# synchronizer_v1_1.net
KiCad netlist of a schematic drawn in EAGLE
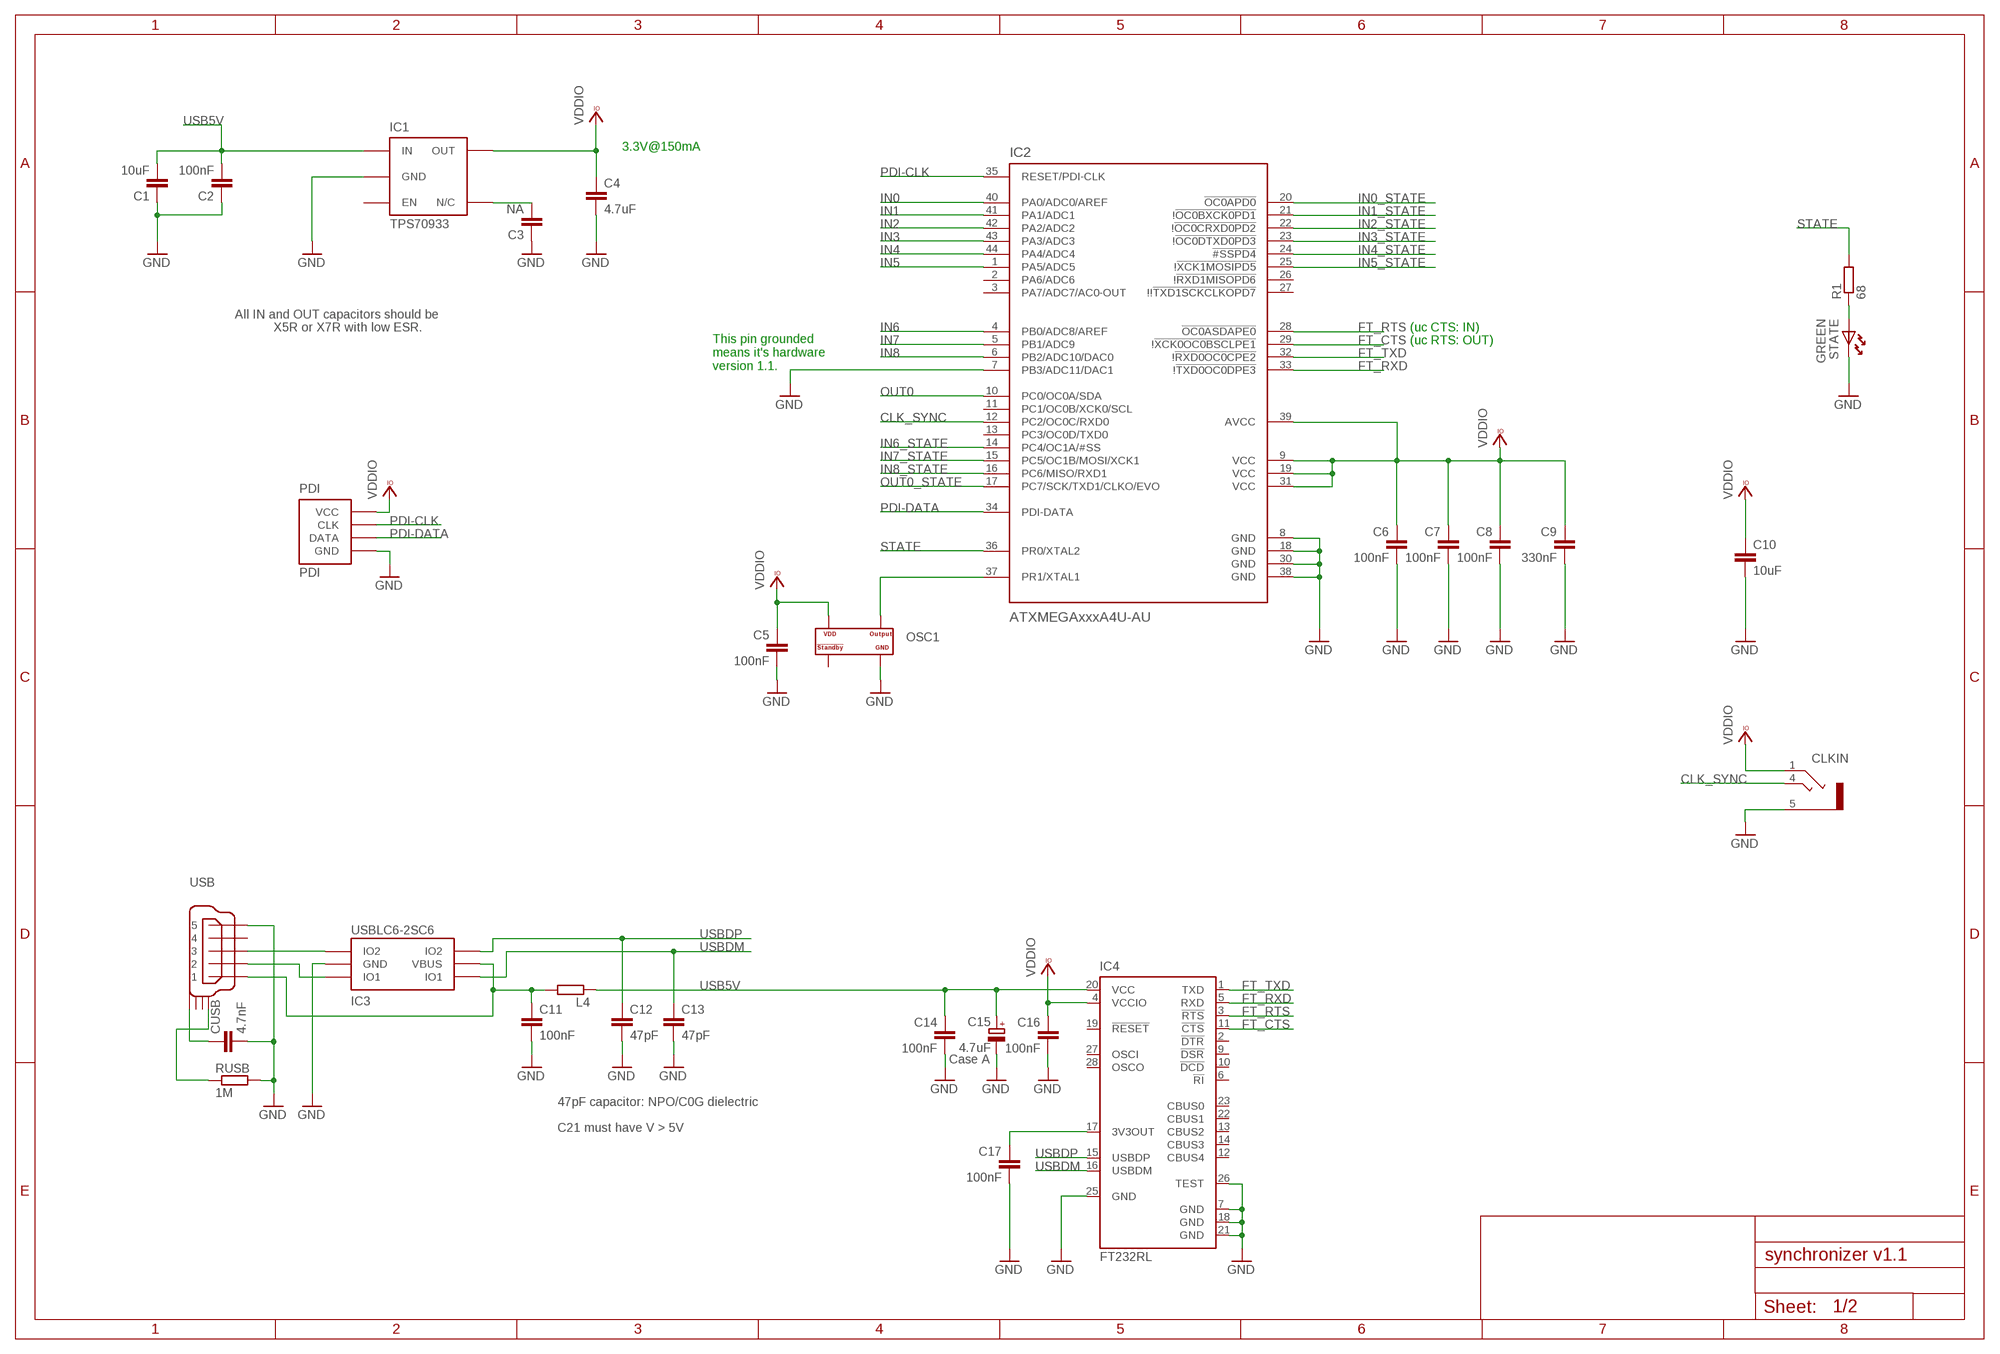
[diagram p0: schematic, sheet 1]
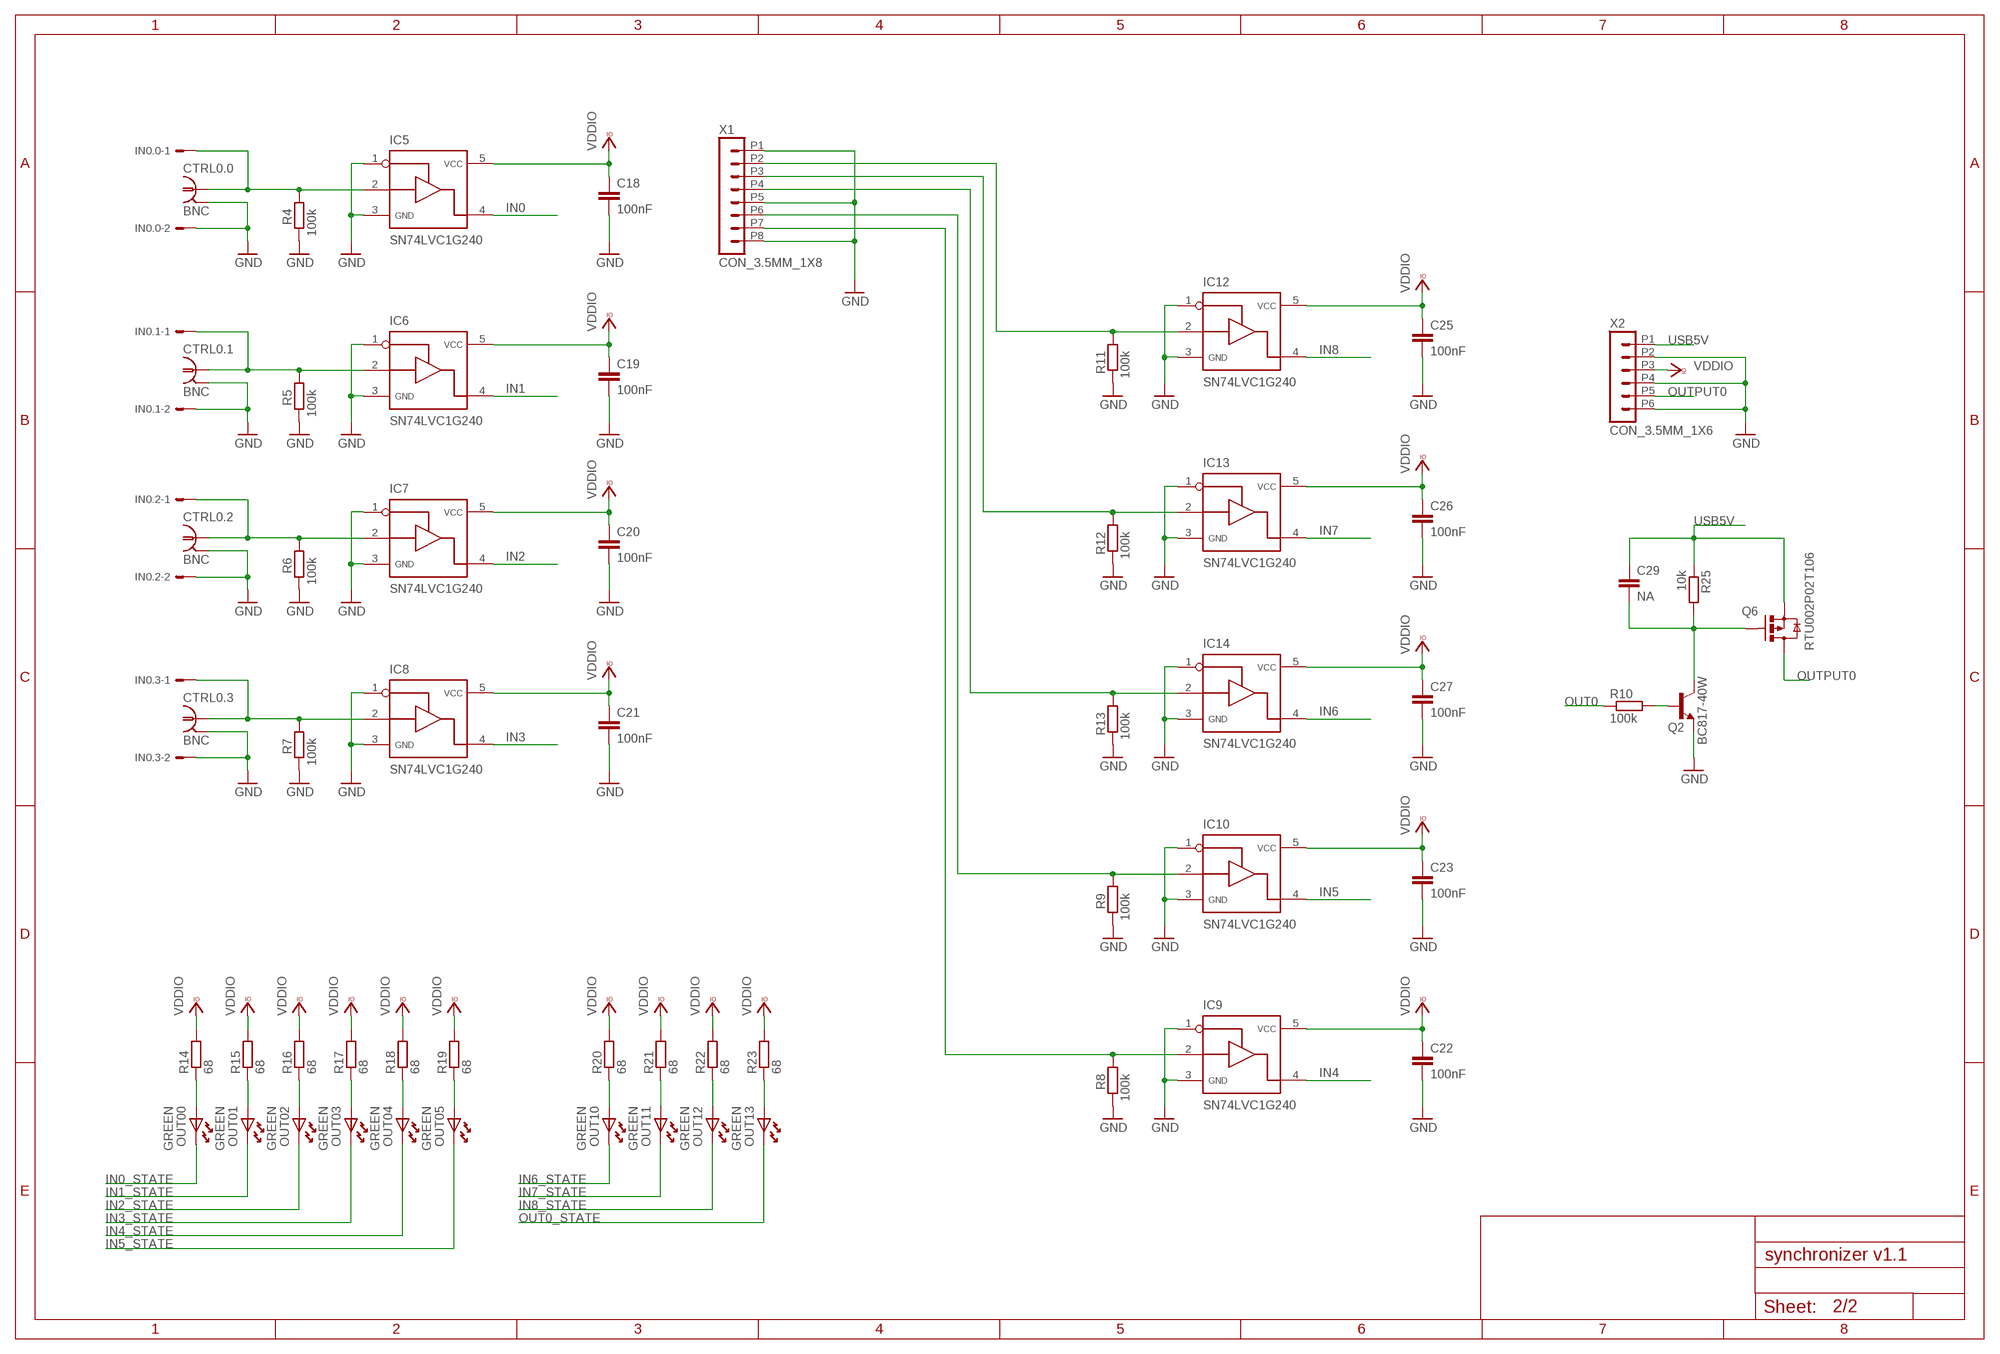
[diagram p1: schematic, sheet 2]

(export (version "E")
  (design (tool "Eeschema 10.0.6"))
  (components
    (comp (ref "C18")
      (value "100nF")
      (footprint "eagle-import:C0402")
      (libsource (lib "eagle-import") (part "C-EUC0402"))
    )
    (comp (ref "C19")
      (value "100nF")
      (footprint "eagle-import:C0402")
      (libsource (lib "eagle-import") (part "C-EUC0402"))
    )
    (comp (ref "C20")
      (value "100nF")
      (footprint "eagle-import:C0402")
      (libsource (lib "eagle-import") (part "C-EUC0402"))
    )
    (comp (ref "C21")
      (value "100nF")
      (footprint "eagle-import:C0402")
      (libsource (lib "eagle-import") (part "C-EUC0402"))
    )
    (comp (ref "C22")
      (value "100nF")
      (footprint "eagle-import:C0402")
      (libsource (lib "eagle-import") (part "C-EUC0402"))
    )
    (comp (ref "C23")
      (value "100nF")
      (footprint "eagle-import:C0402")
      (libsource (lib "eagle-import") (part "C-EUC0402"))
    )
    (comp (ref "C25")
      (value "100nF")
      (footprint "eagle-import:C0402")
      (libsource (lib "eagle-import") (part "C-EUC0402"))
    )
    (comp (ref "C26")
      (value "100nF")
      (footprint "eagle-import:C0402")
      (libsource (lib "eagle-import") (part "C-EUC0402"))
    )
    (comp (ref "C27")
      (value "100nF")
      (footprint "eagle-import:C0402")
      (libsource (lib "eagle-import") (part "C-EUC0402"))
    )
    (comp (ref "C29")
      (value "NA")
      (footprint "eagle-import:C0402")
      (libsource (lib "eagle-import") (part "C-EUC0402"))
    )
    (comp (ref "CTRL0.0")
      (value "BNC")
      (footprint "eagle-import:BNC_RA")
      (libsource (lib "eagle-import") (part "BNC"))
    )
    (comp (ref "CTRL0.1")
      (value "BNC")
      (footprint "eagle-import:BNC_RA")
      (libsource (lib "eagle-import") (part "BNC"))
    )
    (comp (ref "CTRL0.2")
      (value "BNC")
      (footprint "eagle-import:BNC_RA")
      (libsource (lib "eagle-import") (part "BNC"))
    )
    (comp (ref "CTRL0.3")
      (value "BNC")
      (footprint "eagle-import:BNC_RA")
      (libsource (lib "eagle-import") (part "BNC"))
    )
    (comp (ref "IC5")
      (value "SN74LVC1G240")
      (footprint "eagle-import:SOT23-5")
      (libsource (lib "eagle-import") (part "SN74LVC1G125"))
    )
    (comp (ref "IC6")
      (value "SN74LVC1G240")
      (footprint "eagle-import:SOT23-5")
      (libsource (lib "eagle-import") (part "SN74LVC1G125"))
    )
    (comp (ref "IC7")
      (value "SN74LVC1G240")
      (footprint "eagle-import:SOT23-5")
      (libsource (lib "eagle-import") (part "SN74LVC1G125"))
    )
    (comp (ref "IC8")
      (value "SN74LVC1G240")
      (footprint "eagle-import:SOT23-5")
      (libsource (lib "eagle-import") (part "SN74LVC1G125"))
    )
    (comp (ref "IC9")
      (value "SN74LVC1G240")
      (footprint "eagle-import:SOT23-5")
      (libsource (lib "eagle-import") (part "SN74LVC1G125"))
    )
    (comp (ref "IC10")
      (value "SN74LVC1G240")
      (footprint "eagle-import:SOT23-5")
      (libsource (lib "eagle-import") (part "SN74LVC1G125"))
    )
    (comp (ref "IC12")
      (value "SN74LVC1G240")
      (footprint "eagle-import:SOT23-5")
      (libsource (lib "eagle-import") (part "SN74LVC1G125"))
    )
    (comp (ref "IC13")
      (value "SN74LVC1G240")
      (footprint "eagle-import:SOT23-5")
      (libsource (lib "eagle-import") (part "SN74LVC1G125"))
    )
    (comp (ref "IC14")
      (value "SN74LVC1G240")
      (footprint "eagle-import:SOT23-5")
      (libsource (lib "eagle-import") (part "SN74LVC1G125"))
    )
    (comp (ref "IN0.0")
      (value "22-05-7028-02")
      (footprint "eagle-import:7395-02")
      (libsource (lib "eagle-import") (part "22-?-0205-7028"))
    )
    (comp (ref "IN0.1")
      (value "22-05-7028-02")
      (footprint "eagle-import:7395-02")
      (libsource (lib "eagle-import") (part "22-?-0205-7028"))
    )
    (comp (ref "IN0.2")
      (value "22-05-7028-02")
      (footprint "eagle-import:7395-02")
      (libsource (lib "eagle-import") (part "22-?-0205-7028"))
    )
    (comp (ref "IN0.3")
      (value "22-05-7028-02")
      (footprint "eagle-import:7395-02")
      (libsource (lib "eagle-import") (part "22-?-0205-7028"))
    )
    (comp (ref "OUT00")
      (value "GREEN")
      (footprint "eagle-import:LED_HAND")
      (libsource (lib "eagle-import") (part "LEDHAND"))
    )
    (comp (ref "OUT01")
      (value "GREEN")
      (footprint "eagle-import:LED_HAND")
      (libsource (lib "eagle-import") (part "LEDHAND"))
    )
    (comp (ref "OUT02")
      (value "GREEN")
      (footprint "eagle-import:LED_HAND")
      (libsource (lib "eagle-import") (part "LEDHAND"))
    )
    (comp (ref "OUT03")
      (value "GREEN")
      (footprint "eagle-import:LED_HAND")
      (libsource (lib "eagle-import") (part "LEDHAND"))
    )
    (comp (ref "OUT04")
      (value "GREEN")
      (footprint "eagle-import:LED_HAND")
      (libsource (lib "eagle-import") (part "LEDHAND"))
    )
    (comp (ref "OUT05")
      (value "GREEN")
      (footprint "eagle-import:LED_HAND")
      (libsource (lib "eagle-import") (part "LEDHAND"))
    )
    (comp (ref "OUT10")
      (value "GREEN")
      (footprint "eagle-import:LED_HAND")
      (libsource (lib "eagle-import") (part "LEDHAND"))
    )
    (comp (ref "OUT11")
      (value "GREEN")
      (footprint "eagle-import:LED_HAND")
      (libsource (lib "eagle-import") (part "LEDHAND"))
    )
    (comp (ref "OUT12")
      (value "GREEN")
      (footprint "eagle-import:LED_HAND")
      (libsource (lib "eagle-import") (part "LEDHAND"))
    )
    (comp (ref "OUT13")
      (value "GREEN")
      (footprint "eagle-import:LED_HAND")
      (libsource (lib "eagle-import") (part "LEDHAND"))
    )
    (comp (ref "Q2")
      (value "BC817-40W")
      (footprint "eagle-import:SOT323-BEC")
      (libsource (lib "eagle-import") (part "BC817"))
    )
    (comp (ref "Q6")
      (value "RTU002P02T106")
      (footprint "eagle-import:SOT323")
      (libsource (lib "eagle-import") (part "MOSFET-PCHANNEL-ROHM"))
    )
    (comp (ref "R4")
      (value "100k")
      (footprint "eagle-import:R0402")
      (libsource (lib "eagle-import") (part "R-EU_R0402"))
    )
    (comp (ref "R5")
      (value "100k")
      (footprint "eagle-import:R0402")
      (libsource (lib "eagle-import") (part "R-EU_R0402"))
    )
    (comp (ref "R6")
      (value "100k")
      (footprint "eagle-import:R0402")
      (libsource (lib "eagle-import") (part "R-EU_R0402"))
    )
    (comp (ref "R7")
      (value "100k")
      (footprint "eagle-import:R0402")
      (libsource (lib "eagle-import") (part "R-EU_R0402"))
    )
    (comp (ref "R8")
      (value "100k")
      (footprint "eagle-import:R0402")
      (libsource (lib "eagle-import") (part "R-EU_R0402"))
    )
    (comp (ref "R9")
      (value "100k")
      (footprint "eagle-import:R0402")
      (libsource (lib "eagle-import") (part "R-EU_R0402"))
    )
    (comp (ref "R10")
      (value "100k")
      (footprint "eagle-import:R0402")
      (libsource (lib "eagle-import") (part "R-EU_R0402"))
    )
    (comp (ref "R11")
      (value "100k")
      (footprint "eagle-import:R0402")
      (libsource (lib "eagle-import") (part "R-EU_R0402"))
    )
    (comp (ref "R12")
      (value "100k")
      (footprint "eagle-import:R0402")
      (libsource (lib "eagle-import") (part "R-EU_R0402"))
    )
    (comp (ref "R13")
      (value "100k")
      (footprint "eagle-import:R0402")
      (libsource (lib "eagle-import") (part "R-EU_R0402"))
    )
    (comp (ref "R14")
      (value "68")
      (footprint "eagle-import:R0402")
      (libsource (lib "eagle-import") (part "R-EU_R0402"))
    )
    (comp (ref "R15")
      (value "68")
      (footprint "eagle-import:R0402")
      (libsource (lib "eagle-import") (part "R-EU_R0402"))
    )
    (comp (ref "R16")
      (value "68")
      (footprint "eagle-import:R0402")
      (libsource (lib "eagle-import") (part "R-EU_R0402"))
    )
    (comp (ref "R17")
      (value "68")
      (footprint "eagle-import:R0402")
      (libsource (lib "eagle-import") (part "R-EU_R0402"))
    )
    (comp (ref "R18")
      (value "68")
      (footprint "eagle-import:R0402")
      (libsource (lib "eagle-import") (part "R-EU_R0402"))
    )
    (comp (ref "R19")
      (value "68")
      (footprint "eagle-import:R0402")
      (libsource (lib "eagle-import") (part "R-EU_R0402"))
    )
    (comp (ref "R20")
      (value "68")
      (footprint "eagle-import:R0402")
      (libsource (lib "eagle-import") (part "R-EU_R0402"))
    )
    (comp (ref "R21")
      (value "68")
      (footprint "eagle-import:R0402")
      (libsource (lib "eagle-import") (part "R-EU_R0402"))
    )
    (comp (ref "R22")
      (value "68")
      (footprint "eagle-import:R0402")
      (libsource (lib "eagle-import") (part "R-EU_R0402"))
    )
    (comp (ref "R23")
      (value "68")
      (footprint "eagle-import:R0402")
      (libsource (lib "eagle-import") (part "R-EU_R0402"))
    )
    (comp (ref "R25")
      (value "10k")
      (footprint "eagle-import:R0402")
      (libsource (lib "eagle-import") (part "R-EU_R0402"))
    )
    (comp (ref "X1")
      (value "CON_3.5MM_1X8")
      (footprint "eagle-import:CON_3.5MM_1X8")
      (libsource (lib "eagle-import") (part "CON_3.5MM_1X8"))
    )
    (comp (ref "X2")
      (value "CON_3.5MM_1X6")
      (footprint "eagle-import:CON_3.5MM_1X6")
      (libsource (lib "eagle-import") (part "CON_3.5MM_1X6"))
    )
    (comp (ref "C1")
      (value "10uF")
      (footprint "eagle-import:C0603")
      (libsource (lib "eagle-import") (part "C-EUC0603"))
    )
    (comp (ref "C2")
      (value "100nF")
      (footprint "eagle-import:C0402")
      (libsource (lib "eagle-import") (part "C-EUC0402"))
    )
    (comp (ref "C3")
      (value "NA")
      (footprint "eagle-import:C0402")
      (libsource (lib "eagle-import") (part "C-EUC0402"))
    )
    (comp (ref "C4")
      (value "4.7uF")
      (footprint "eagle-import:C0603")
      (libsource (lib "eagle-import") (part "C-EUC0603"))
    )
    (comp (ref "C5")
      (value "100nF")
      (footprint "eagle-import:C0402")
      (libsource (lib "eagle-import") (part "C-EUC0402"))
    )
    (comp (ref "C6")
      (value "100nF")
      (footprint "eagle-import:C0402")
      (libsource (lib "eagle-import") (part "C-EUC0402"))
    )
    (comp (ref "C7")
      (value "100nF")
      (footprint "eagle-import:C0402")
      (libsource (lib "eagle-import") (part "C-EUC0402"))
    )
    (comp (ref "C8")
      (value "100nF")
      (footprint "eagle-import:C0402")
      (libsource (lib "eagle-import") (part "C-EUC0402"))
    )
    (comp (ref "C9")
      (value "330nF")
      (footprint "eagle-import:C0402")
      (libsource (lib "eagle-import") (part "C-EUC0402"))
    )
    (comp (ref "C10")
      (value "10uF")
      (footprint "eagle-import:C0603")
      (libsource (lib "eagle-import") (part "C-EUC0603"))
    )
    (comp (ref "C11")
      (value "100nF")
      (footprint "eagle-import:C0402")
      (libsource (lib "eagle-import") (part "C-EUC0402"))
    )
    (comp (ref "C12")
      (value "47pF")
      (footprint "eagle-import:C0402")
      (libsource (lib "eagle-import") (part "C-EUC0402"))
    )
    (comp (ref "C13")
      (value "47pF")
      (footprint "eagle-import:C0402")
      (libsource (lib "eagle-import") (part "C-EUC0402"))
    )
    (comp (ref "C14")
      (value "100nF")
      (footprint "eagle-import:C0402")
      (libsource (lib "eagle-import") (part "C-EUC0402"))
    )
    (comp (ref "C15")
      (value "4.7uF")
      (footprint "eagle-import:A_3216-18W")
      (libsource (lib "eagle-import") (part "CPOL-EUA/3216-18W"))
    )
    (comp (ref "C16")
      (value "100nF")
      (footprint "eagle-import:C0402")
      (libsource (lib "eagle-import") (part "C-EUC0402"))
    )
    (comp (ref "C17")
      (value "100nF")
      (footprint "eagle-import:C0402")
      (libsource (lib "eagle-import") (part "C-EUC0402"))
    )
    (comp (ref "CLKIN")
      (value "STEREO_JACK")
      (footprint "eagle-import:35RASMT2BHNTRX")
      (libsource (lib "eagle-import") (part "STEREO_JACK"))
    )
    (comp (ref "CUSB")
      (value "4.7nF")
      (footprint "eagle-import:C0402")
      (libsource (lib "eagle-import") (part "C-EUC0402"))
    )
    (comp (ref "IC1")
      (value "TPS70933")
      (footprint "eagle-import:TSOT23-5")
      (libsource (lib "eagle-import") (part "TLV700XX"))
    )
    (comp (ref "IC2")
      (value "ATXMEGAxxxA4U-AU")
      (footprint "eagle-import:QFP80P1200X1200X120-44N")
      (libsource (lib "eagle-import") (part "AT-XMEGA-XXA4-AU"))
    )
    (comp (ref "IC3")
      (value "USBLC6-2SC6")
      (footprint "eagle-import:SOT23-6L")
      (libsource (lib "eagle-import") (part "USBLC6-2"))
    )
    (comp (ref "IC4")
      (value "FT232RL")
      (footprint "eagle-import:SSOP28")
      (libsource (lib "eagle-import") (part "FT232RL"))
    )
    (comp (ref "L4")
      (value "???")
      (footprint "eagle-import:R0805")
      (libsource (lib "eagle-import") (part "R-EU_R0805"))
    )
    (comp (ref "OSC1")
      (value "OSCILLATOR")
      (footprint "eagle-import:OSCILLATOR_3.2X2.5")
      (libsource (lib "eagle-import") (part "OSCILLATOR"))
    )
    (comp (ref "PDI")
      (value "PDI")
      (footprint "eagle-import:PDI_2.54_1X4")
      (libsource (lib "eagle-import") (part "PDI"))
    )
    (comp (ref "R1")
      (value "68")
      (footprint "eagle-import:R0402")
      (libsource (lib "eagle-import") (part "R-EU_R0402"))
    )
    (comp (ref "RUSB")
      (value "1M")
      (footprint "eagle-import:R0603")
      (libsource (lib "eagle-import") (part "R-EU_R0603"))
    )
    (comp (ref "STATE")
      (value "GREEN")
      (footprint "eagle-import:LED_HAND")
      (libsource (lib "eagle-import") (part "LEDHAND"))
    )
    (comp (ref "USB")
      (value "USB_MINI_B")
      (footprint "eagle-import:240-0002-1")
      (libsource (lib "eagle-import") (part "USB_MINI_B"))
    )
  )
  (nets
    (net (code "1") (name "CLK_SYNC") (class "Default")
      (node (ref "CLKIN") (pin "4") (pinfunction "4_4") (pintype "passive"))
      (node (ref "IC2") (pin "12") (pinfunction "PC2/OC0C/RXD0_12") (pintype "bidirectional"))
    )
    (net (code "2") (name "FT_CTS") (class "Default")
      (node (ref "IC2") (pin "29") (pinfunction "~XCK0OC0BSCLPE1_29") (pintype "bidirectional"))
      (node (ref "IC4") (pin "11") (pinfunction "~{CTS}_11") (pintype "input"))
    )
    (net (code "3") (name "FT_RTS") (class "Default")
      (node (ref "IC2") (pin "28") (pinfunction "~{OC0ASDAPE0}_28") (pintype "bidirectional"))
      (node (ref "IC4") (pin "3") (pinfunction "~{RTS}_3") (pintype "output"))
    )
    (net (code "4") (name "FT_RXD") (class "Default")
      (node (ref "IC2") (pin "33") (pinfunction "~TXD0OC0DPE3_33") (pintype "bidirectional"))
      (node (ref "IC4") (pin "5") (pinfunction "RXD_5") (pintype "input"))
    )
    (net (code "5") (name "FT_TXD") (class "Default")
      (node (ref "IC2") (pin "32") (pinfunction "~RXD0OC0CPE2_32") (pintype "bidirectional"))
      (node (ref "IC4") (pin "1") (pinfunction "TXD_1") (pintype "output"))
    )
    (net (code "6") (name "GND") (class "Default")
      (node (ref "C1") (pin "1") (pinfunction "1_1") (pintype "passive"))
      (node (ref "C10") (pin "2") (pinfunction "2_2") (pintype "passive"))
      (node (ref "C11") (pin "2") (pinfunction "2_2") (pintype "passive"))
      (node (ref "C12") (pin "2") (pinfunction "2_2") (pintype "passive"))
      (node (ref "C13") (pin "2") (pinfunction "2_2") (pintype "passive"))
      (node (ref "C14") (pin "2") (pinfunction "2_2") (pintype "passive"))
      (node (ref "C15") (pin "-") (pinfunction "-_-") (pintype "passive"))
      (node (ref "C16") (pin "2") (pinfunction "2_2") (pintype "passive"))
      (node (ref "C17") (pin "2") (pinfunction "2_2") (pintype "passive"))
      (node (ref "C18") (pin "2") (pinfunction "2_2") (pintype "passive"))
      (node (ref "C19") (pin "2") (pinfunction "2_2") (pintype "passive"))
      (node (ref "C2") (pin "1") (pinfunction "1_1") (pintype "passive"))
      (node (ref "C20") (pin "2") (pinfunction "2_2") (pintype "passive"))
      (node (ref "C21") (pin "2") (pinfunction "2_2") (pintype "passive"))
      (node (ref "C22") (pin "2") (pinfunction "2_2") (pintype "passive"))
      (node (ref "C23") (pin "2") (pinfunction "2_2") (pintype "passive"))
      (node (ref "C25") (pin "2") (pinfunction "2_2") (pintype "passive"))
      (node (ref "C26") (pin "2") (pinfunction "2_2") (pintype "passive"))
      (node (ref "C27") (pin "2") (pinfunction "2_2") (pintype "passive"))
      (node (ref "C3") (pin "1") (pinfunction "1_1") (pintype "passive"))
      (node (ref "C4") (pin "2") (pinfunction "2_2") (pintype "passive"))
      (node (ref "C5") (pin "2") (pinfunction "2_2") (pintype "passive"))
      (node (ref "C6") (pin "2") (pinfunction "2_2") (pintype "passive"))
      (node (ref "C7") (pin "2") (pinfunction "2_2") (pintype "passive"))
      (node (ref "C8") (pin "2") (pinfunction "2_2") (pintype "passive"))
      (node (ref "C9") (pin "2") (pinfunction "2_2") (pintype "passive"))
      (node (ref "CLKIN") (pin "5") (pinfunction "5_5") (pintype "passive"))
      (node (ref "CTRL0.0") (pin "2") (pinfunction "2_2") (pintype "passive"))
      (node (ref "CTRL0.1") (pin "2") (pinfunction "2_2") (pintype "passive"))
      (node (ref "CTRL0.2") (pin "2") (pinfunction "2_2") (pintype "passive"))
      (node (ref "CTRL0.3") (pin "2") (pinfunction "2_2") (pintype "passive"))
      (node (ref "CUSB") (pin "2") (pinfunction "2_2") (pintype "passive"))
      (node (ref "IC1") (pin "2") (pinfunction "GND_2") (pintype "bidirectional"))
      (node (ref "IC10") (pin "1") (pinfunction "P$1_1") (pintype "bidirectional"))
      (node (ref "IC10") (pin "3") (pinfunction "P$3_3") (pintype "bidirectional"))
      (node (ref "IC12") (pin "1") (pinfunction "P$1_1") (pintype "bidirectional"))
      (node (ref "IC12") (pin "3") (pinfunction "P$3_3") (pintype "bidirectional"))
      (node (ref "IC13") (pin "1") (pinfunction "P$1_1") (pintype "bidirectional"))
      (node (ref "IC13") (pin "3") (pinfunction "P$3_3") (pintype "bidirectional"))
      (node (ref "IC14") (pin "1") (pinfunction "P$1_1") (pintype "bidirectional"))
      (node (ref "IC14") (pin "3") (pinfunction "P$3_3") (pintype "bidirectional"))
      (node (ref "IC2") (pin "18") (pinfunction "GND_18") (pintype "power_in"))
      (node (ref "IC2") (pin "30") (pinfunction "GND_30") (pintype "power_in"))
      (node (ref "IC2") (pin "38") (pinfunction "GND_38") (pintype "power_in"))
      (node (ref "IC2") (pin "7") (pinfunction "PB3/ADC11/DAC1_7") (pintype "bidirectional"))
      (node (ref "IC2") (pin "8") (pinfunction "GND_8") (pintype "power_in"))
      (node (ref "IC3") (pin "P$2") (pinfunction "GND_P$2") (pintype "bidirectional"))
      (node (ref "IC4") (pin "18") (pinfunction "GND_18") (pintype "power_in"))
      (node (ref "IC4") (pin "21") (pinfunction "GND_21") (pintype "power_in"))
      (node (ref "IC4") (pin "25") (pinfunction "GND_25") (pintype "power_in"))
      (node (ref "IC4") (pin "26") (pinfunction "TEST_26") (pintype "input"))
      (node (ref "IC4") (pin "7") (pinfunction "GND_7") (pintype "power_in"))
      (node (ref "IC5") (pin "1") (pinfunction "P$1_1") (pintype "bidirectional"))
      (node (ref "IC5") (pin "3") (pinfunction "P$3_3") (pintype "bidirectional"))
      (node (ref "IC6") (pin "1") (pinfunction "P$1_1") (pintype "bidirectional"))
      (node (ref "IC6") (pin "3") (pinfunction "P$3_3") (pintype "bidirectional"))
      (node (ref "IC7") (pin "1") (pinfunction "P$1_1") (pintype "bidirectional"))
      (node (ref "IC7") (pin "3") (pinfunction "P$3_3") (pintype "bidirectional"))
      (node (ref "IC8") (pin "1") (pinfunction "P$1_1") (pintype "bidirectional"))
      (node (ref "IC8") (pin "3") (pinfunction "P$3_3") (pintype "bidirectional"))
      (node (ref "IC9") (pin "1") (pinfunction "P$1_1") (pintype "bidirectional"))
      (node (ref "IC9") (pin "3") (pinfunction "P$3_3") (pintype "bidirectional"))
      (node (ref "IN0.0") (pin "2") (pinfunction "S_2") (pintype "passive"))
      (node (ref "IN0.1") (pin "2") (pinfunction "S_2") (pintype "passive"))
      (node (ref "IN0.2") (pin "2") (pinfunction "S_2") (pintype "passive"))
      (node (ref "IN0.3") (pin "2") (pinfunction "S_2") (pintype "passive"))
      (node (ref "OSC1") (pin "P$2") (pinfunction "GND_P$2") (pintype "passive"))
      (node (ref "PDI") (pin "P$1") (pinfunction "GND_P$1") (pintype "bidirectional"))
      (node (ref "Q2") (pin "E") (pinfunction "E_E") (pintype "passive"))
      (node (ref "R11") (pin "2") (pinfunction "2_2") (pintype "passive"))
      (node (ref "R12") (pin "2") (pinfunction "2_2") (pintype "passive"))
      (node (ref "R13") (pin "2") (pinfunction "2_2") (pintype "passive"))
      (node (ref "R4") (pin "2") (pinfunction "2_2") (pintype "passive"))
      (node (ref "R5") (pin "2") (pinfunction "2_2") (pintype "passive"))
      (node (ref "R6") (pin "2") (pinfunction "2_2") (pintype "passive"))
      (node (ref "R7") (pin "2") (pinfunction "2_2") (pintype "passive"))
      (node (ref "R8") (pin "2") (pinfunction "2_2") (pintype "passive"))
      (node (ref "R9") (pin "2") (pinfunction "2_2") (pintype "passive"))
      (node (ref "RUSB") (pin "2") (pinfunction "2_2") (pintype "passive"))
      (node (ref "STATE") (pin "K") (pinfunction "K_K") (pintype "bidirectional"))
      (node (ref "USB") (pin "P$5") (pinfunction "5_P$5") (pintype "bidirectional"))
      (node (ref "X1") (pin "P1") (pinfunction "1_P1") (pintype "passive"))
      (node (ref "X1") (pin "P5") (pinfunction "5_P5") (pintype "passive"))
      (node (ref "X1") (pin "P8") (pinfunction "8_P8") (pintype "passive"))
      (node (ref "X2") (pin "P2") (pinfunction "2_P2") (pintype "passive"))
      (node (ref "X2") (pin "P4") (pinfunction "4_P4") (pintype "passive"))
      (node (ref "X2") (pin "P6") (pinfunction "6_P6") (pintype "passive"))
    )
    (net (code "7") (name "IN0") (class "Default")
      (node (ref "IC2") (pin "40") (pinfunction "PA0/ADC0/AREF_40") (pintype "bidirectional"))
      (node (ref "IC5") (pin "4") (pinfunction "P$4_4") (pintype "bidirectional"))
    )
    (net (code "8") (name "IN0_STATE") (class "Default")
      (node (ref "IC2") (pin "20") (pinfunction "~{OC0APD0}_20") (pintype "bidirectional"))
      (node (ref "OUT00") (pin "K") (pinfunction "K_K") (pintype "bidirectional"))
    )
    (net (code "9") (name "IN1") (class "Default")
      (node (ref "IC2") (pin "41") (pinfunction "PA1/ADC1_41") (pintype "bidirectional"))
      (node (ref "IC6") (pin "4") (pinfunction "P$4_4") (pintype "bidirectional"))
    )
    (net (code "10") (name "IN1_STATE") (class "Default")
      (node (ref "IC2") (pin "21") (pinfunction "~OC0BXCK0PD1_21") (pintype "bidirectional"))
      (node (ref "OUT01") (pin "K") (pinfunction "K_K") (pintype "bidirectional"))
    )
    (net (code "11") (name "IN2") (class "Default")
      (node (ref "IC2") (pin "42") (pinfunction "PA2/ADC2_42") (pintype "bidirectional"))
      (node (ref "IC7") (pin "4") (pinfunction "P$4_4") (pintype "bidirectional"))
    )
    (net (code "12") (name "IN2_STATE") (class "Default")
      (node (ref "IC2") (pin "22") (pinfunction "~OC0CRXD0PD2_22") (pintype "bidirectional"))
      (node (ref "OUT02") (pin "K") (pinfunction "K_K") (pintype "bidirectional"))
    )
    (net (code "13") (name "IN3") (class "Default")
      (node (ref "IC2") (pin "43") (pinfunction "PA3/ADC3_43") (pintype "bidirectional"))
      (node (ref "IC8") (pin "4") (pinfunction "P$4_4") (pintype "bidirectional"))
    )
    (net (code "14") (name "IN3_STATE") (class "Default")
      (node (ref "IC2") (pin "23") (pinfunction "~OC0DTXD0PD3_23") (pintype "bidirectional"))
      (node (ref "OUT03") (pin "K") (pinfunction "K_K") (pintype "bidirectional"))
    )
    (net (code "15") (name "IN4") (class "Default")
      (node (ref "IC2") (pin "44") (pinfunction "PA4/ADC4_44") (pintype "bidirectional"))
      (node (ref "IC9") (pin "4") (pinfunction "P$4_4") (pintype "bidirectional"))
    )
    (net (code "16") (name "IN4_STATE") (class "Default")
      (node (ref "IC2") (pin "24") (pinfunction "~{#SSPD4}_24") (pintype "bidirectional"))
      (node (ref "OUT04") (pin "K") (pinfunction "K_K") (pintype "bidirectional"))
    )
    (net (code "17") (name "IN5") (class "Default")
      (node (ref "IC10") (pin "4") (pinfunction "P$4_4") (pintype "bidirectional"))
      (node (ref "IC2") (pin "1") (pinfunction "PA5/ADC5_1") (pintype "bidirectional"))
    )
    (net (code "18") (name "IN5_STATE") (class "Default")
      (node (ref "IC2") (pin "25") (pinfunction "~XCK1MOSIPD5_25") (pintype "bidirectional"))
      (node (ref "OUT05") (pin "K") (pinfunction "K_K") (pintype "bidirectional"))
    )
    (net (code "19") (name "IN6") (class "Default")
      (node (ref "IC14") (pin "4") (pinfunction "P$4_4") (pintype "bidirectional"))
      (node (ref "IC2") (pin "4") (pinfunction "PB0/ADC8/AREF_4") (pintype "bidirectional"))
    )
    (net (code "20") (name "IN6_STATE") (class "Default")
      (node (ref "IC2") (pin "14") (pinfunction "PC4/OC1A/#SS_14") (pintype "bidirectional"))
      (node (ref "OUT10") (pin "K") (pinfunction "K_K") (pintype "bidirectional"))
    )
    (net (code "21") (name "IN7") (class "Default")
      (node (ref "IC13") (pin "4") (pinfunction "P$4_4") (pintype "bidirectional"))
      (node (ref "IC2") (pin "5") (pinfunction "PB1/ADC9_5") (pintype "bidirectional"))
    )
    (net (code "22") (name "IN7_STATE") (class "Default")
      (node (ref "IC2") (pin "15") (pinfunction "PC5/OC1B/MOSI/XCK1_15") (pintype "bidirectional"))
      (node (ref "OUT11") (pin "K") (pinfunction "K_K") (pintype "bidirectional"))
    )
    (net (code "23") (name "IN8") (class "Default")
      (node (ref "IC12") (pin "4") (pinfunction "P$4_4") (pintype "bidirectional"))
      (node (ref "IC2") (pin "6") (pinfunction "PB2/ADC10/DAC0_6") (pintype "bidirectional"))
    )
    (net (code "24") (name "IN8_STATE") (class "Default")
      (node (ref "IC2") (pin "16") (pinfunction "PC6/MISO/RXD1_16") (pintype "bidirectional"))
      (node (ref "OUT12") (pin "K") (pinfunction "K_K") (pintype "bidirectional"))
    )
    (net (code "25") (name "Net-(IC1-N{slash}C)") (class "Default")
      (node (ref "C3") (pin "2") (pinfunction "2_2") (pintype "passive"))
      (node (ref "IC1") (pin "4") (pinfunction "N/C_4") (pintype "bidirectional"))
    )
    (net (code "26") (name "Net-(IC2-PR1{slash}XTAL1)") (class "Default")
      (node (ref "IC2") (pin "37") (pinfunction "PR1/XTAL1_37") (pintype "bidirectional"))
      (node (ref "OSC1") (pin "P$3") (pinfunction "OUTPUT_P$3") (pintype "passive"))
    )
    (net (code "27") (name "Net-(IC3-VBUS)") (class "Default")
      (node (ref "C11") (pin "1") (pinfunction "1_1") (pintype "passive"))
      (node (ref "IC3") (pin "P$5") (pinfunction "VBUS_P$5") (pintype "bidirectional"))
      (node (ref "L4") (pin "2") (pinfunction "2_2") (pintype "passive"))
      (node (ref "USB") (pin "P$1") (pinfunction "1_P$1") (pintype "bidirectional"))
    )
    (net (code "28") (name "Net-(IC4-3V3OUT)") (class "Default")
      (node (ref "C17") (pin "1") (pinfunction "1_1") (pintype "passive"))
      (node (ref "IC4") (pin "17") (pinfunction "3V3OUT_17") (pintype "output"))
    )
    (net (code "29") (name "Net-(IC5-P$2)") (class "Default")
      (node (ref "CTRL0.0") (pin "1") (pinfunction "1_1") (pintype "passive"))
      (node (ref "IC5") (pin "2") (pinfunction "P$2_2") (pintype "bidirectional"))
      (node (ref "IN0.0") (pin "1") (pinfunction "S_1") (pintype "passive"))
      (node (ref "R4") (pin "1") (pinfunction "1_1") (pintype "passive"))
    )
    (net (code "30") (name "Net-(IC6-P$2)") (class "Default")
      (node (ref "CTRL0.1") (pin "1") (pinfunction "1_1") (pintype "passive"))
      (node (ref "IC6") (pin "2") (pinfunction "P$2_2") (pintype "bidirectional"))
      (node (ref "IN0.1") (pin "1") (pinfunction "S_1") (pintype "passive"))
      (node (ref "R5") (pin "1") (pinfunction "1_1") (pintype "passive"))
    )
    (net (code "31") (name "Net-(IC7-P$2)") (class "Default")
      (node (ref "CTRL0.2") (pin "1") (pinfunction "1_1") (pintype "passive"))
      (node (ref "IC7") (pin "2") (pinfunction "P$2_2") (pintype "bidirectional"))
      (node (ref "IN0.2") (pin "1") (pinfunction "S_1") (pintype "passive"))
      (node (ref "R6") (pin "1") (pinfunction "1_1") (pintype "passive"))
    )
    (net (code "32") (name "Net-(IC8-P$2)") (class "Default")
      (node (ref "CTRL0.3") (pin "1") (pinfunction "1_1") (pintype "passive"))
      (node (ref "IC8") (pin "2") (pinfunction "P$2_2") (pintype "bidirectional"))
      (node (ref "IN0.3") (pin "1") (pinfunction "S_1") (pintype "passive"))
      (node (ref "R7") (pin "1") (pinfunction "1_1") (pintype "passive"))
    )
    (net (code "33") (name "Net-(IC9-P$2)") (class "Default")
      (node (ref "IC9") (pin "2") (pinfunction "P$2_2") (pintype "bidirectional"))
      (node (ref "R8") (pin "1") (pinfunction "1_1") (pintype "passive"))
      (node (ref "X1") (pin "P7") (pinfunction "7_P7") (pintype "passive"))
    )
    (net (code "34") (name "Net-(IC10-P$2)") (class "Default")
      (node (ref "IC10") (pin "2") (pinfunction "P$2_2") (pintype "bidirectional"))
      (node (ref "R9") (pin "1") (pinfunction "1_1") (pintype "passive"))
      (node (ref "X1") (pin "P6") (pinfunction "6_P6") (pintype "passive"))
    )
    (net (code "35") (name "Net-(IC12-P$2)") (class "Default")
      (node (ref "IC12") (pin "2") (pinfunction "P$2_2") (pintype "bidirectional"))
      (node (ref "R11") (pin "1") (pinfunction "1_1") (pintype "passive"))
      (node (ref "X1") (pin "P2") (pinfunction "2_P2") (pintype "passive"))
    )
    (net (code "36") (name "Net-(IC13-P$2)") (class "Default")
      (node (ref "IC13") (pin "2") (pinfunction "P$2_2") (pintype "bidirectional"))
      (node (ref "R12") (pin "1") (pinfunction "1_1") (pintype "passive"))
      (node (ref "X1") (pin "P3") (pinfunction "3_P3") (pintype "passive"))
    )
    (net (code "37") (name "Net-(IC14-P$2)") (class "Default")
      (node (ref "IC14") (pin "2") (pinfunction "P$2_2") (pintype "bidirectional"))
      (node (ref "R13") (pin "1") (pinfunction "1_1") (pintype "passive"))
      (node (ref "X1") (pin "P4") (pinfunction "4_P4") (pintype "passive"))
    )
    (net (code "38") (name "Net-(OUT00-PadA)") (class "Default")
      (node (ref "OUT00") (pin "A") (pinfunction "A_A") (pintype "bidirectional"))
      (node (ref "R14") (pin "1") (pinfunction "1_1") (pintype "passive"))
    )
    (net (code "39") (name "Net-(OUT01-PadA)") (class "Default")
      (node (ref "OUT01") (pin "A") (pinfunction "A_A") (pintype "bidirectional"))
      (node (ref "R15") (pin "1") (pinfunction "1_1") (pintype "passive"))
    )
    (net (code "40") (name "Net-(OUT02-PadA)") (class "Default")
      (node (ref "OUT02") (pin "A") (pinfunction "A_A") (pintype "bidirectional"))
      (node (ref "R16") (pin "1") (pinfunction "1_1") (pintype "passive"))
    )
    (net (code "41") (name "Net-(OUT03-PadA)") (class "Default")
      (node (ref "OUT03") (pin "A") (pinfunction "A_A") (pintype "bidirectional"))
      (node (ref "R17") (pin "1") (pinfunction "1_1") (pintype "passive"))
    )
    (net (code "42") (name "Net-(OUT04-PadA)") (class "Default")
      (node (ref "OUT04") (pin "A") (pinfunction "A_A") (pintype "bidirectional"))
      (node (ref "R18") (pin "1") (pinfunction "1_1") (pintype "passive"))
    )
    (net (code "43") (name "Net-(OUT05-PadA)") (class "Default")
      (node (ref "OUT05") (pin "A") (pinfunction "A_A") (pintype "bidirectional"))
      (node (ref "R19") (pin "1") (pinfunction "1_1") (pintype "passive"))
    )
    (net (code "44") (name "Net-(OUT10-PadA)") (class "Default")
      (node (ref "OUT10") (pin "A") (pinfunction "A_A") (pintype "bidirectional"))
      (node (ref "R20") (pin "1") (pinfunction "1_1") (pintype "passive"))
    )
    (net (code "45") (name "Net-(OUT11-PadA)") (class "Default")
      (node (ref "OUT11") (pin "A") (pinfunction "A_A") (pintype "bidirectional"))
      (node (ref "R21") (pin "1") (pinfunction "1_1") (pintype "passive"))
    )
    (net (code "46") (name "Net-(OUT12-PadA)") (class "Default")
      (node (ref "OUT12") (pin "A") (pinfunction "A_A") (pintype "bidirectional"))
      (node (ref "R22") (pin "1") (pinfunction "1_1") (pintype "passive"))
    )
    (net (code "47") (name "Net-(OUT13-PadA)") (class "Default")
      (node (ref "OUT13") (pin "A") (pinfunction "A_A") (pintype "bidirectional"))
      (node (ref "R23") (pin "1") (pinfunction "1_1") (pintype "passive"))
    )
    (net (code "48") (name "Net-(Q2-PadB)") (class "Default")
      (node (ref "Q2") (pin "B") (pinfunction "B_B") (pintype "passive"))
      (node (ref "R10") (pin "2") (pinfunction "2_2") (pintype "passive"))
    )
    (net (code "49") (name "Net-(Q6-G)") (class "Default")
      (node (ref "C29") (pin "2") (pinfunction "2_2") (pintype "passive"))
      (node (ref "Q2") (pin "C") (pinfunction "C_C") (pintype "passive"))
      (node (ref "Q6") (pin "2") (pinfunction "G_2") (pintype "passive"))
      (node (ref "R25") (pin "2") (pinfunction "2_2") (pintype "passive"))
    )
    (net (code "50") (name "Net-(R1-Pad1)") (class "Default")
      (node (ref "R1") (pin "1") (pinfunction "1_1") (pintype "passive"))
      (node (ref "STATE") (pin "A") (pinfunction "A_A") (pintype "bidirectional"))
    )
    (net (code "51") (name "Net-(USB-2)") (class "Default")
      (node (ref "IC3") (pin "P$1") (pinfunction "IO1_P$1") (pintype "bidirectional"))
      (node (ref "USB") (pin "P$2") (pinfunction "2_P$2") (pintype "bidirectional"))
    )
    (net (code "52") (name "Net-(USB-3)") (class "Default")
      (node (ref "IC3") (pin "P$3") (pinfunction "IO2_P$3") (pintype "bidirectional"))
      (node (ref "USB") (pin "P$3") (pinfunction "3_P$3") (pintype "bidirectional"))
    )
    (net (code "53") (name "Net-(USB-P$1)") (class "Default")
      (node (ref "RUSB") (pin "1") (pinfunction "1_1") (pintype "passive"))
      (node (ref "USB") (pin "SHIELD_1") (pinfunction "P$1_SHIELD_1") (pintype "bidirectional"))
    )
    (net (code "54") (name "Net-(USB-P$4)") (class "Default")
      (node (ref "CUSB") (pin "1") (pinfunction "1_1") (pintype "passive"))
      (node (ref "USB") (pin "SHIELD_4") (pinfunction "P$4_SHIELD_4") (pintype "bidirectional"))
    )
    (net (code "55") (name "OUT0") (class "Default")
      (node (ref "IC2") (pin "10") (pinfunction "PC0/OC0A/SDA_10") (pintype "bidirectional"))
      (node (ref "R10") (pin "1") (pinfunction "1_1") (pintype "passive"))
    )
    (net (code "56") (name "OUT0_STATE") (class "Default")
      (node (ref "IC2") (pin "17") (pinfunction "PC7/SCK/TXD1/CLKO/EVO_17") (pintype "bidirectional"))
      (node (ref "OUT13") (pin "K") (pinfunction "K_K") (pintype "bidirectional"))
    )
    (net (code "57") (name "OUTPUT0") (class "Default")
      (node (ref "Q6") (pin "3") (pinfunction "D_3") (pintype "passive"))
      (node (ref "X2") (pin "P5") (pinfunction "5_P5") (pintype "passive"))
    )
    (net (code "58") (name "PDI-CLK") (class "Default")
      (node (ref "IC2") (pin "35") (pinfunction "RESET/PDI-CLK_35") (pintype "input"))
      (node (ref "PDI") (pin "P$3") (pinfunction "CLK_P$3") (pintype "bidirectional"))
    )
    (net (code "59") (name "PDI-DATA") (class "Default")
      (node (ref "IC2") (pin "34") (pinfunction "PDI-DATA_34") (pintype "bidirectional"))
      (node (ref "PDI") (pin "P$2") (pinfunction "DATA_P$2") (pintype "bidirectional"))
    )
    (net (code "60") (name "STATE") (class "Default")
      (node (ref "IC2") (pin "36") (pinfunction "PR0/XTAL2_36") (pintype "bidirectional"))
      (node (ref "R1") (pin "2") (pinfunction "2_2") (pintype "passive"))
    )
    (net (code "61") (name "USB5V") (class "Default")
      (node (ref "C1") (pin "2") (pinfunction "2_2") (pintype "passive"))
      (node (ref "C14") (pin "1") (pinfunction "1_1") (pintype "passive"))
      (node (ref "C15") (pin "+") (pinfunction "+_+") (pintype "passive"))
      (node (ref "C2") (pin "2") (pinfunction "2_2") (pintype "passive"))
      (node (ref "C29") (pin "1") (pinfunction "1_1") (pintype "passive"))
      (node (ref "IC1") (pin "1") (pinfunction "IN_1") (pintype "bidirectional"))
      (node (ref "IC4") (pin "20") (pinfunction "VCC_20") (pintype "power_in"))
      (node (ref "L4") (pin "1") (pinfunction "1_1") (pintype "passive"))
      (node (ref "Q6") (pin "1") (pinfunction "S_1") (pintype "passive"))
      (node (ref "R25") (pin "1") (pinfunction "1_1") (pintype "passive"))
      (node (ref "X2") (pin "P1") (pinfunction "1_P1") (pintype "passive"))
    )
    (net (code "62") (name "USBDM") (class "Default")
      (node (ref "C13") (pin "1") (pinfunction "1_1") (pintype "passive"))
      (node (ref "IC3") (pin "P$6") (pinfunction "IO1_P$6") (pintype "bidirectional"))
      (node (ref "IC4") (pin "16") (pinfunction "USBDM_16") (pintype "bidirectional"))
    )
    (net (code "63") (name "USBDP") (class "Default")
      (node (ref "C12") (pin "1") (pinfunction "1_1") (pintype "passive"))
      (node (ref "IC3") (pin "P$4") (pinfunction "IO2_P$4") (pintype "bidirectional"))
      (node (ref "IC4") (pin "15") (pinfunction "USBDP_15") (pintype "bidirectional"))
    )
    (net (code "64") (name "VCCIO") (class "Default")
      (node (ref "C10") (pin "1") (pinfunction "1_1") (pintype "passive"))
      (node (ref "C16") (pin "1") (pinfunction "1_1") (pintype "passive"))
      (node (ref "C18") (pin "1") (pinfunction "1_1") (pintype "passive"))
      (node (ref "C19") (pin "1") (pinfunction "1_1") (pintype "passive"))
      (node (ref "C20") (pin "1") (pinfunction "1_1") (pintype "passive"))
      (node (ref "C21") (pin "1") (pinfunction "1_1") (pintype "passive"))
      (node (ref "C22") (pin "1") (pinfunction "1_1") (pintype "passive"))
      (node (ref "C23") (pin "1") (pinfunction "1_1") (pintype "passive"))
      (node (ref "C25") (pin "1") (pinfunction "1_1") (pintype "passive"))
      (node (ref "C26") (pin "1") (pinfunction "1_1") (pintype "passive"))
      (node (ref "C27") (pin "1") (pinfunction "1_1") (pintype "passive"))
      (node (ref "C4") (pin "1") (pinfunction "1_1") (pintype "passive"))
      (node (ref "C5") (pin "1") (pinfunction "1_1") (pintype "passive"))
      (node (ref "C6") (pin "1") (pinfunction "1_1") (pintype "passive"))
      (node (ref "C7") (pin "1") (pinfunction "1_1") (pintype "passive"))
      (node (ref "C8") (pin "1") (pinfunction "1_1") (pintype "passive"))
      (node (ref "C9") (pin "1") (pinfunction "1_1") (pintype "passive"))
      (node (ref "CLKIN") (pin "1") (pinfunction "1_1") (pintype "passive"))
      (node (ref "IC1") (pin "5") (pinfunction "OUT_5") (pintype "bidirectional"))
      (node (ref "IC10") (pin "5") (pinfunction "P$5_5") (pintype "bidirectional"))
      (node (ref "IC12") (pin "5") (pinfunction "P$5_5") (pintype "bidirectional"))
      (node (ref "IC13") (pin "5") (pinfunction "P$5_5") (pintype "bidirectional"))
      (node (ref "IC14") (pin "5") (pinfunction "P$5_5") (pintype "bidirectional"))
      (node (ref "IC2") (pin "19") (pinfunction "VCC_19") (pintype "power_in"))
      (node (ref "IC2") (pin "31") (pinfunction "VCC_31") (pintype "power_in"))
      (node (ref "IC2") (pin "39") (pinfunction "AVCC_39") (pintype "power_in"))
      (node (ref "IC2") (pin "9") (pinfunction "VCC_9") (pintype "power_in"))
      (node (ref "IC4") (pin "4") (pinfunction "VCCIO_4") (pintype "power_in"))
      (node (ref "IC5") (pin "5") (pinfunction "P$5_5") (pintype "bidirectional"))
      (node (ref "IC6") (pin "5") (pinfunction "P$5_5") (pintype "bidirectional"))
      (node (ref "IC7") (pin "5") (pinfunction "P$5_5") (pintype "bidirectional"))
      (node (ref "IC8") (pin "5") (pinfunction "P$5_5") (pintype "bidirectional"))
      (node (ref "IC9") (pin "5") (pinfunction "P$5_5") (pintype "bidirectional"))
      (node (ref "OSC1") (pin "P$4") (pinfunction "VDD_P$4") (pintype "passive"))
      (node (ref "PDI") (pin "P$4") (pinfunction "VCC_P$4") (pintype "bidirectional"))
      (node (ref "R14") (pin "2") (pinfunction "2_2") (pintype "passive"))
      (node (ref "R15") (pin "2") (pinfunction "2_2") (pintype "passive"))
      (node (ref "R16") (pin "2") (pinfunction "2_2") (pintype "passive"))
      (node (ref "R17") (pin "2") (pinfunction "2_2") (pintype "passive"))
      (node (ref "R18") (pin "2") (pinfunction "2_2") (pintype "passive"))
      (node (ref "R19") (pin "2") (pinfunction "2_2") (pintype "passive"))
      (node (ref "R20") (pin "2") (pinfunction "2_2") (pintype "passive"))
      (node (ref "R21") (pin "2") (pinfunction "2_2") (pintype "passive"))
      (node (ref "R22") (pin "2") (pinfunction "2_2") (pintype "passive"))
      (node (ref "R23") (pin "2") (pinfunction "2_2") (pintype "passive"))
      (node (ref "X2") (pin "P3") (pinfunction "3_P3") (pintype "passive"))
    )
    (net (code "65") (name "unconnected-(IC1-EN-Pad3)") (class "Default")
      (node (ref "IC1") (pin "3") (pinfunction "EN_3") (pintype "bidirectional"))
    )
    (net (code "66") (name "unconnected-(IC2-PA6{slash}ADC6-Pad2)") (class "Default")
      (node (ref "IC2") (pin "2") (pinfunction "PA6/ADC6_2") (pintype "bidirectional"))
    )
    (net (code "67") (name "unconnected-(IC2-PA7{slash}ADC7{slash}AC0-OUT-Pad3)") (class "Default")
      (node (ref "IC2") (pin "3") (pinfunction "PA7/ADC7/AC0-OUT_3") (pintype "bidirectional"))
    )
    (net (code "68") (name "unconnected-(IC2-PC1{slash}OC0B{slash}XCK0{slash}SCL-Pad11)") (class "Default")
      (node (ref "IC2") (pin "11") (pinfunction "PC1/OC0B/XCK0/SCL_11") (pintype "bidirectional"))
    )
    (net (code "69") (name "unconnected-(IC2-PC3{slash}OC0D{slash}TXD0-Pad13)") (class "Default")
      (node (ref "IC2") (pin "13") (pinfunction "PC3/OC0D/TXD0_13") (pintype "bidirectional"))
    )
    (net (code "70") (name "unconnected-(IC2-~RXD1MISOPD6-Pad26)") (class "Default")
      (node (ref "IC2") (pin "26") (pinfunction "~RXD1MISOPD6_26") (pintype "bidirectional"))
    )
    (net (code "71") (name "unconnected-(IC2-~~{TXD1SCKCLKOPD7}-Pad27)") (class "Default")
      (node (ref "IC2") (pin "27") (pinfunction "~~{TXD1SCKCLKOPD7}_27") (pintype "bidirectional"))
    )
    (net (code "72") (name "unconnected-(IC4-CBUS0-Pad23)") (class "Default")
      (node (ref "IC4") (pin "23") (pinfunction "CBUS0_23") (pintype "bidirectional"))
    )
    (net (code "73") (name "unconnected-(IC4-CBUS1-Pad22)") (class "Default")
      (node (ref "IC4") (pin "22") (pinfunction "CBUS1_22") (pintype "bidirectional"))
    )
    (net (code "74") (name "unconnected-(IC4-CBUS2-Pad13)") (class "Default")
      (node (ref "IC4") (pin "13") (pinfunction "CBUS2_13") (pintype "bidirectional"))
    )
    (net (code "75") (name "unconnected-(IC4-CBUS3-Pad14)") (class "Default")
      (node (ref "IC4") (pin "14") (pinfunction "CBUS3_14") (pintype "bidirectional"))
    )
    (net (code "76") (name "unconnected-(IC4-CBUS4-Pad12)") (class "Default")
      (node (ref "IC4") (pin "12") (pinfunction "CBUS4_12") (pintype "bidirectional"))
    )
    (net (code "77") (name "unconnected-(IC4-OSCI-Pad27)") (class "Default")
      (node (ref "IC4") (pin "27") (pinfunction "OSCI_27") (pintype "input"))
    )
    (net (code "78") (name "unconnected-(IC4-OSCO-Pad28)") (class "Default")
      (node (ref "IC4") (pin "28") (pinfunction "OSCO_28") (pintype "output"))
    )
    (net (code "79") (name "unconnected-(IC4-~{DCD}-Pad10)") (class "Default")
      (node (ref "IC4") (pin "10") (pinfunction "~{DCD}_10") (pintype "input"))
    )
    (net (code "80") (name "unconnected-(IC4-~{DSR}-Pad9)") (class "Default")
      (node (ref "IC4") (pin "9") (pinfunction "~{DSR}_9") (pintype "input"))
    )
    (net (code "81") (name "unconnected-(IC4-~{DTR}-Pad2)") (class "Default")
      (node (ref "IC4") (pin "2") (pinfunction "~{DTR}_2") (pintype "output"))
    )
    (net (code "82") (name "unconnected-(IC4-~{RESET}-Pad19)") (class "Default")
      (node (ref "IC4") (pin "19") (pinfunction "~{RESET}_19") (pintype "input"))
    )
    (net (code "83") (name "unconnected-(IC4-~{RI}-Pad6)") (class "Default")
      (node (ref "IC4") (pin "6") (pinfunction "~{RI}_6") (pintype "input"))
    )
    (net (code "84") (name "unconnected-(OSC1-STANDBY#-PadP$1)") (class "Default")
      (node (ref "OSC1") (pin "P$1") (pinfunction "STANDBY#_P$1") (pintype "passive"))
    )
    (net (code "85") (name "unconnected-(USB-4-PadP$4)") (class "Default")
      (node (ref "USB") (pin "P$4") (pinfunction "4_P$4") (pintype "bidirectional"))
    )
    (net (code "86") (name "unconnected-(USB-P$2-PadSHIELD_2)") (class "Default")
      (node (ref "USB") (pin "SHIELD_2") (pinfunction "P$2_SHIELD_2") (pintype "bidirectional"))
    )
    (net (code "87") (name "unconnected-(USB-P$3-PadSHIELD_3)") (class "Default")
      (node (ref "USB") (pin "SHIELD_3") (pinfunction "P$3_SHIELD_3") (pintype "bidirectional"))
    )
  )
)
